# relay_board.net
KiCad netlist of a schematic drawn in EAGLE
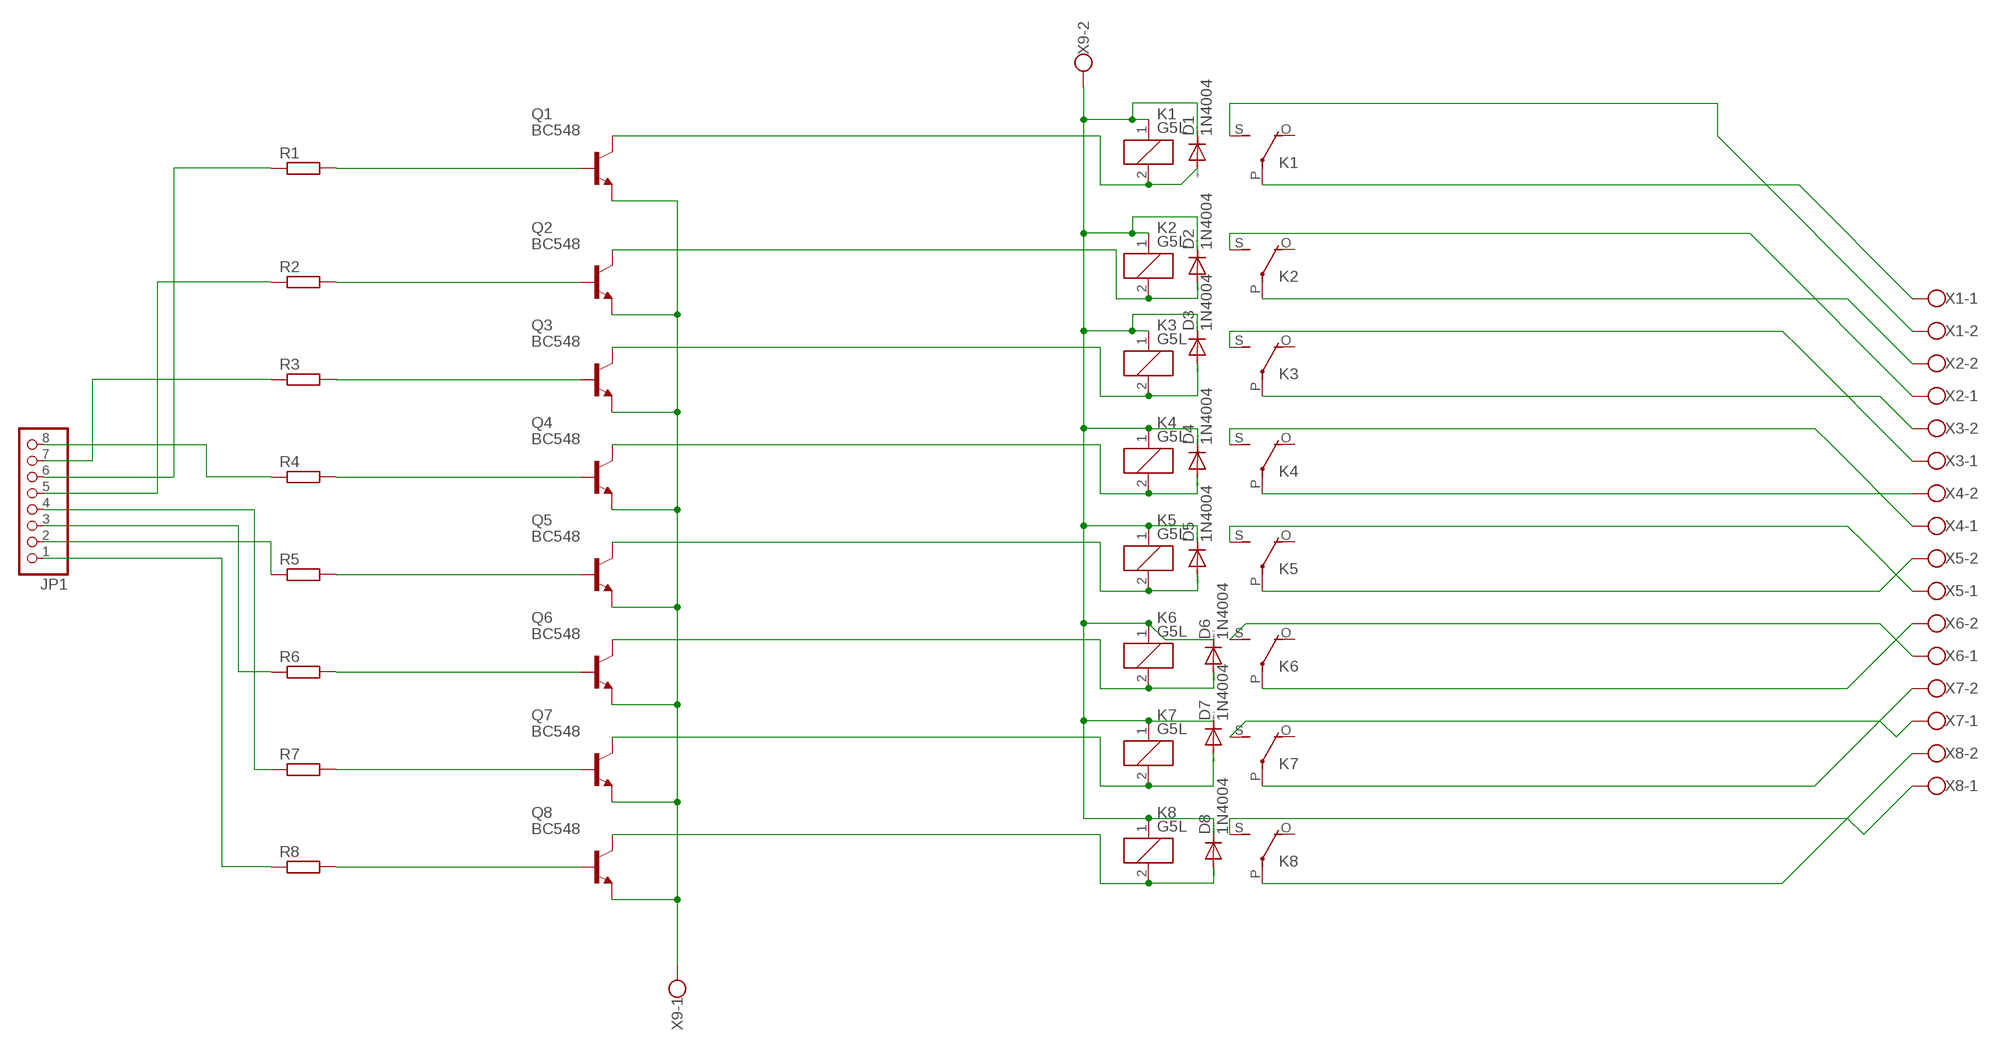
[diagram p0: schematic, sheet 1]

(export (version "E")
  (design (tool "Eeschema 10.0.6"))
  (components
    (comp (ref "D1")
      (value "1N4004")
      (footprint "eagle-import:DO41-10")
      (libsource (lib "eagle-import") (part "1N4004"))
    )
    (comp (ref "D2")
      (value "1N4004")
      (footprint "eagle-import:DO41-10")
      (libsource (lib "eagle-import") (part "1N4004"))
    )
    (comp (ref "D3")
      (value "1N4004")
      (footprint "eagle-import:DO41-10")
      (libsource (lib "eagle-import") (part "1N4004"))
    )
    (comp (ref "D4")
      (value "1N4004")
      (footprint "eagle-import:DO41-10")
      (libsource (lib "eagle-import") (part "1N4004"))
    )
    (comp (ref "D5")
      (value "1N4004")
      (footprint "eagle-import:DO41-10")
      (libsource (lib "eagle-import") (part "1N4004"))
    )
    (comp (ref "D6")
      (value "1N4004")
      (footprint "eagle-import:DO41-10")
      (libsource (lib "eagle-import") (part "1N4004"))
    )
    (comp (ref "D7")
      (value "1N4004")
      (footprint "eagle-import:DO41-10")
      (libsource (lib "eagle-import") (part "1N4004"))
    )
    (comp (ref "D8")
      (value "1N4004")
      (footprint "eagle-import:DO41-10")
      (libsource (lib "eagle-import") (part "1N4004"))
    )
    (comp (ref "JP1")
      (value "PINHD-1X8")
      (footprint "eagle-import:1X08")
      (libsource (lib "eagle-import") (part "PINHD-1X8"))
    )
    (comp (ref "K1")
      (value "G5L")
      (footprint "eagle-import:G5LE")
      (libsource (lib "eagle-import") (part "G5L"))
    )
    (comp (ref "K2")
      (value "G5L")
      (footprint "eagle-import:G5LE")
      (libsource (lib "eagle-import") (part "G5L"))
    )
    (comp (ref "K3")
      (value "G5L")
      (footprint "eagle-import:G5LE")
      (libsource (lib "eagle-import") (part "G5L"))
    )
    (comp (ref "K4")
      (value "G5L")
      (footprint "eagle-import:G5LE")
      (libsource (lib "eagle-import") (part "G5L"))
    )
    (comp (ref "K5")
      (value "G5L")
      (footprint "eagle-import:G5LE")
      (libsource (lib "eagle-import") (part "G5L"))
    )
    (comp (ref "K6")
      (value "G5L")
      (footprint "eagle-import:G5LE")
      (libsource (lib "eagle-import") (part "G5L"))
    )
    (comp (ref "K7")
      (value "G5L")
      (footprint "eagle-import:G5LE")
      (libsource (lib "eagle-import") (part "G5L"))
    )
    (comp (ref "K8")
      (value "G5L")
      (footprint "eagle-import:G5LE")
      (libsource (lib "eagle-import") (part "G5L"))
    )
    (comp (ref "Q1")
      (value "BC548")
      (footprint "eagle-import:TO92-EBC")
      (libsource (lib "eagle-import") (part "BC548"))
    )
    (comp (ref "Q2")
      (value "BC548")
      (footprint "eagle-import:TO92-EBC")
      (libsource (lib "eagle-import") (part "BC548"))
    )
    (comp (ref "Q3")
      (value "BC548")
      (footprint "eagle-import:TO92-EBC")
      (libsource (lib "eagle-import") (part "BC548"))
    )
    (comp (ref "Q4")
      (value "BC548")
      (footprint "eagle-import:TO92-EBC")
      (libsource (lib "eagle-import") (part "BC548"))
    )
    (comp (ref "Q5")
      (value "BC548")
      (footprint "eagle-import:TO92-EBC")
      (libsource (lib "eagle-import") (part "BC548"))
    )
    (comp (ref "Q6")
      (value "BC548")
      (footprint "eagle-import:TO92-EBC")
      (libsource (lib "eagle-import") (part "BC548"))
    )
    (comp (ref "Q7")
      (value "BC548")
      (footprint "eagle-import:TO92-EBC")
      (libsource (lib "eagle-import") (part "BC548"))
    )
    (comp (ref "Q8")
      (value "BC548")
      (footprint "eagle-import:TO92-EBC")
      (libsource (lib "eagle-import") (part "BC548"))
    )
    (comp (ref "R1")
      (value "RCL_R-EU_0207/10")
      (footprint "eagle-import:RCL_0207_10")
      (libsource (lib "eagle-import") (part "RCL_R-EU_0207/10"))
    )
    (comp (ref "R2")
      (value "RCL_R-EU_0207/10")
      (footprint "eagle-import:RCL_0207_10")
      (libsource (lib "eagle-import") (part "RCL_R-EU_0207/10"))
    )
    (comp (ref "R3")
      (value "RCL_R-EU_0207/10")
      (footprint "eagle-import:RCL_0207_10")
      (libsource (lib "eagle-import") (part "RCL_R-EU_0207/10"))
    )
    (comp (ref "R4")
      (value "RCL_R-EU_0207/10")
      (footprint "eagle-import:RCL_0207_10")
      (libsource (lib "eagle-import") (part "RCL_R-EU_0207/10"))
    )
    (comp (ref "R5")
      (value "RCL_R-EU_0207/10")
      (footprint "eagle-import:RCL_0207_10")
      (libsource (lib "eagle-import") (part "RCL_R-EU_0207/10"))
    )
    (comp (ref "R6")
      (value "RCL_R-EU_0207/10")
      (footprint "eagle-import:RCL_0207_10")
      (libsource (lib "eagle-import") (part "RCL_R-EU_0207/10"))
    )
    (comp (ref "R7")
      (value "RCL_R-EU_0207/10")
      (footprint "eagle-import:RCL_0207_10")
      (libsource (lib "eagle-import") (part "RCL_R-EU_0207/10"))
    )
    (comp (ref "R8")
      (value "RCL_R-EU_0207/10")
      (footprint "eagle-import:RCL_0207_10")
      (libsource (lib "eagle-import") (part "RCL_R-EU_0207/10"))
    )
    (comp (ref "X1")
      (value "W237-102")
      (footprint "eagle-import:W237-102")
      (fields (field (name "MPN") "237-102"))
      (libsource (lib "eagle-import") (part "W237-102"))
    )
    (comp (ref "X2")
      (value "W237-102")
      (footprint "eagle-import:W237-102")
      (fields (field (name "MPN") "237-102"))
      (libsource (lib "eagle-import") (part "W237-102"))
    )
    (comp (ref "X3")
      (value "W237-102")
      (footprint "eagle-import:W237-102")
      (fields (field (name "MPN") "237-102"))
      (libsource (lib "eagle-import") (part "W237-102"))
    )
    (comp (ref "X4")
      (value "W237-102")
      (footprint "eagle-import:W237-102")
      (fields (field (name "MPN") "237-102"))
      (libsource (lib "eagle-import") (part "W237-102"))
    )
    (comp (ref "X5")
      (value "W237-102")
      (footprint "eagle-import:W237-102")
      (fields (field (name "MPN") "237-102"))
      (libsource (lib "eagle-import") (part "W237-102"))
    )
    (comp (ref "X6")
      (value "W237-102")
      (footprint "eagle-import:W237-102")
      (fields (field (name "MPN") "237-102"))
      (libsource (lib "eagle-import") (part "W237-102"))
    )
    (comp (ref "X7")
      (value "W237-102")
      (footprint "eagle-import:W237-102")
      (fields (field (name "MPN") "237-102"))
      (libsource (lib "eagle-import") (part "W237-102"))
    )
    (comp (ref "X8")
      (value "W237-102")
      (footprint "eagle-import:W237-102")
      (fields (field (name "MPN") "237-102"))
      (libsource (lib "eagle-import") (part "W237-102"))
    )
    (comp (ref "X9")
      (value "W237-102")
      (footprint "eagle-import:W237-102")
      (fields (field (name "MPN") "237-102"))
      (libsource (lib "eagle-import") (part "W237-102"))
    )
  )
  (nets
    (net (code "1") (name "Net-(D1-PadA)") (class "Default")
      (node (ref "D1") (pin "A") (pinfunction "A_A") (pintype "passive"))
      (node (ref "K1") (pin "2") (pinfunction "2_2") (pintype "passive"))
      (node (ref "Q1") (pin "C") (pinfunction "C_C") (pintype "passive"))
    )
    (net (code "2") (name "Net-(D2-PadA)") (class "Default")
      (node (ref "D2") (pin "A") (pinfunction "A_A") (pintype "passive"))
      (node (ref "K2") (pin "2") (pinfunction "2_2") (pintype "passive"))
      (node (ref "Q2") (pin "C") (pinfunction "C_C") (pintype "passive"))
    )
    (net (code "3") (name "Net-(D3-PadA)") (class "Default")
      (node (ref "D3") (pin "A") (pinfunction "A_A") (pintype "passive"))
      (node (ref "K3") (pin "2") (pinfunction "2_2") (pintype "passive"))
      (node (ref "Q3") (pin "C") (pinfunction "C_C") (pintype "passive"))
    )
    (net (code "4") (name "Net-(D4-PadA)") (class "Default")
      (node (ref "D4") (pin "A") (pinfunction "A_A") (pintype "passive"))
      (node (ref "K4") (pin "2") (pinfunction "2_2") (pintype "passive"))
      (node (ref "Q4") (pin "C") (pinfunction "C_C") (pintype "passive"))
    )
    (net (code "5") (name "Net-(D5-PadA)") (class "Default")
      (node (ref "D5") (pin "A") (pinfunction "A_A") (pintype "passive"))
      (node (ref "K5") (pin "2") (pinfunction "2_2") (pintype "passive"))
      (node (ref "Q5") (pin "C") (pinfunction "C_C") (pintype "passive"))
    )
    (net (code "6") (name "Net-(D6-PadA)") (class "Default")
      (node (ref "D6") (pin "A") (pinfunction "A_A") (pintype "passive"))
      (node (ref "K6") (pin "2") (pinfunction "2_2") (pintype "passive"))
      (node (ref "Q6") (pin "C") (pinfunction "C_C") (pintype "passive"))
    )
    (net (code "7") (name "Net-(D7-PadA)") (class "Default")
      (node (ref "D7") (pin "A") (pinfunction "A_A") (pintype "passive"))
      (node (ref "K7") (pin "2") (pinfunction "2_2") (pintype "passive"))
      (node (ref "Q7") (pin "C") (pinfunction "C_C") (pintype "passive"))
    )
    (net (code "8") (name "Net-(D8-PadA)") (class "Default")
      (node (ref "D8") (pin "A") (pinfunction "A_A") (pintype "passive"))
      (node (ref "K8") (pin "2") (pinfunction "2_2") (pintype "passive"))
      (node (ref "Q8") (pin "C") (pinfunction "C_C") (pintype "passive"))
    )
    (net (code "9") (name "Net-(JP1-Pad1)") (class "Default")
      (node (ref "JP1") (pin "1") (pinfunction "1_1") (pintype "passive"))
      (node (ref "R8") (pin "1") (pinfunction "1_1") (pintype "passive"))
    )
    (net (code "10") (name "Net-(JP1-Pad2)") (class "Default")
      (node (ref "JP1") (pin "2") (pinfunction "2_2") (pintype "passive"))
      (node (ref "R5") (pin "1") (pinfunction "1_1") (pintype "passive"))
    )
    (net (code "11") (name "Net-(JP1-Pad3)") (class "Default")
      (node (ref "JP1") (pin "3") (pinfunction "3_3") (pintype "passive"))
      (node (ref "R6") (pin "1") (pinfunction "1_1") (pintype "passive"))
    )
    (net (code "12") (name "Net-(JP1-Pad4)") (class "Default")
      (node (ref "JP1") (pin "4") (pinfunction "4_4") (pintype "passive"))
      (node (ref "R7") (pin "1") (pinfunction "1_1") (pintype "passive"))
    )
    (net (code "13") (name "Net-(JP1-Pad5)") (class "Default")
      (node (ref "JP1") (pin "5") (pinfunction "5_5") (pintype "passive"))
      (node (ref "R2") (pin "1") (pinfunction "1_1") (pintype "passive"))
    )
    (net (code "14") (name "Net-(JP1-Pad6)") (class "Default")
      (node (ref "JP1") (pin "6") (pinfunction "6_6") (pintype "passive"))
      (node (ref "R1") (pin "1") (pinfunction "1_1") (pintype "passive"))
    )
    (net (code "15") (name "Net-(JP1-Pad7)") (class "Default")
      (node (ref "JP1") (pin "7") (pinfunction "7_7") (pintype "passive"))
      (node (ref "R3") (pin "1") (pinfunction "1_1") (pintype "passive"))
    )
    (net (code "16") (name "Net-(JP1-Pad8)") (class "Default")
      (node (ref "JP1") (pin "8") (pinfunction "8_8") (pintype "passive"))
      (node (ref "R4") (pin "1") (pinfunction "1_1") (pintype "passive"))
    )
    (net (code "17") (name "Net-(Q1-PadB)") (class "Default")
      (node (ref "Q1") (pin "B") (pinfunction "B_B") (pintype "passive"))
      (node (ref "R1") (pin "2") (pinfunction "2_2") (pintype "passive"))
    )
    (net (code "18") (name "Net-(Q2-PadB)") (class "Default")
      (node (ref "Q2") (pin "B") (pinfunction "B_B") (pintype "passive"))
      (node (ref "R2") (pin "2") (pinfunction "2_2") (pintype "passive"))
    )
    (net (code "19") (name "Net-(Q3-PadB)") (class "Default")
      (node (ref "Q3") (pin "B") (pinfunction "B_B") (pintype "passive"))
      (node (ref "R3") (pin "2") (pinfunction "2_2") (pintype "passive"))
    )
    (net (code "20") (name "Net-(Q4-PadB)") (class "Default")
      (node (ref "Q4") (pin "B") (pinfunction "B_B") (pintype "passive"))
      (node (ref "R4") (pin "2") (pinfunction "2_2") (pintype "passive"))
    )
    (net (code "21") (name "Net-(Q5-PadB)") (class "Default")
      (node (ref "Q5") (pin "B") (pinfunction "B_B") (pintype "passive"))
      (node (ref "R5") (pin "2") (pinfunction "2_2") (pintype "passive"))
    )
    (net (code "22") (name "Net-(Q6-PadB)") (class "Default")
      (node (ref "Q6") (pin "B") (pinfunction "B_B") (pintype "passive"))
      (node (ref "R6") (pin "2") (pinfunction "2_2") (pintype "passive"))
    )
    (net (code "23") (name "Net-(Q7-PadB)") (class "Default")
      (node (ref "Q7") (pin "B") (pinfunction "B_B") (pintype "passive"))
      (node (ref "R7") (pin "2") (pinfunction "2_2") (pintype "passive"))
    )
    (net (code "24") (name "Net-(Q8-PadB)") (class "Default")
      (node (ref "Q8") (pin "B") (pinfunction "B_B") (pintype "passive"))
      (node (ref "R8") (pin "2") (pinfunction "2_2") (pintype "passive"))
    )
    (net (code "25") (name "Net-(X1A-KL)") (class "Default")
      (node (ref "K1") (pin "P") (pinfunction "P_P") (pintype "passive"))
      (node (ref "X1") (pin "1") (pinfunction "KL_1") (pintype "passive"))
    )
    (net (code "26") (name "Net-(X1B-KL)") (class "Default")
      (node (ref "K1") (pin "S") (pinfunction "S_S") (pintype "passive"))
      (node (ref "X1") (pin "2") (pinfunction "KL_2") (pintype "passive"))
    )
    (net (code "27") (name "Net-(X2A-KL)") (class "Default")
      (node (ref "K2") (pin "S") (pinfunction "S_S") (pintype "passive"))
      (node (ref "X2") (pin "1") (pinfunction "KL_1") (pintype "passive"))
    )
    (net (code "28") (name "Net-(X2B-KL)") (class "Default")
      (node (ref "K2") (pin "P") (pinfunction "P_P") (pintype "passive"))
      (node (ref "X2") (pin "2") (pinfunction "KL_2") (pintype "passive"))
    )
    (net (code "29") (name "Net-(X3A-KL)") (class "Default")
      (node (ref "K3") (pin "S") (pinfunction "S_S") (pintype "passive"))
      (node (ref "X3") (pin "1") (pinfunction "KL_1") (pintype "passive"))
    )
    (net (code "30") (name "Net-(X3B-KL)") (class "Default")
      (node (ref "K3") (pin "P") (pinfunction "P_P") (pintype "passive"))
      (node (ref "X3") (pin "2") (pinfunction "KL_2") (pintype "passive"))
    )
    (net (code "31") (name "Net-(X4A-KL)") (class "Default")
      (node (ref "K4") (pin "S") (pinfunction "S_S") (pintype "passive"))
      (node (ref "X4") (pin "1") (pinfunction "KL_1") (pintype "passive"))
    )
    (net (code "32") (name "Net-(X4B-KL)") (class "Default")
      (node (ref "K4") (pin "P") (pinfunction "P_P") (pintype "passive"))
      (node (ref "X4") (pin "2") (pinfunction "KL_2") (pintype "passive"))
    )
    (net (code "33") (name "Net-(X5A-KL)") (class "Default")
      (node (ref "K5") (pin "S") (pinfunction "S_S") (pintype "passive"))
      (node (ref "X5") (pin "1") (pinfunction "KL_1") (pintype "passive"))
    )
    (net (code "34") (name "Net-(X5B-KL)") (class "Default")
      (node (ref "K5") (pin "P") (pinfunction "P_P") (pintype "passive"))
      (node (ref "X5") (pin "2") (pinfunction "KL_2") (pintype "passive"))
    )
    (net (code "35") (name "Net-(X6A-KL)") (class "Default")
      (node (ref "K6") (pin "S") (pinfunction "S_S") (pintype "passive"))
      (node (ref "X6") (pin "1") (pinfunction "KL_1") (pintype "passive"))
    )
    (net (code "36") (name "Net-(X6B-KL)") (class "Default")
      (node (ref "K6") (pin "P") (pinfunction "P_P") (pintype "passive"))
      (node (ref "X6") (pin "2") (pinfunction "KL_2") (pintype "passive"))
    )
    (net (code "37") (name "Net-(X7A-KL)") (class "Default")
      (node (ref "K7") (pin "S") (pinfunction "S_S") (pintype "passive"))
      (node (ref "X7") (pin "1") (pinfunction "KL_1") (pintype "passive"))
    )
    (net (code "38") (name "Net-(X7B-KL)") (class "Default")
      (node (ref "K7") (pin "P") (pinfunction "P_P") (pintype "passive"))
      (node (ref "X7") (pin "2") (pinfunction "KL_2") (pintype "passive"))
    )
    (net (code "39") (name "Net-(X8A-KL)") (class "Default")
      (node (ref "K8") (pin "S") (pinfunction "S_S") (pintype "passive"))
      (node (ref "X8") (pin "1") (pinfunction "KL_1") (pintype "passive"))
    )
    (net (code "40") (name "Net-(X8B-KL)") (class "Default")
      (node (ref "K8") (pin "P") (pinfunction "P_P") (pintype "passive"))
      (node (ref "X8") (pin "2") (pinfunction "KL_2") (pintype "passive"))
    )
    (net (code "41") (name "Net-(X9A-KL)") (class "Default")
      (node (ref "Q1") (pin "E") (pinfunction "E_E") (pintype "passive"))
      (node (ref "Q2") (pin "E") (pinfunction "E_E") (pintype "passive"))
      (node (ref "Q3") (pin "E") (pinfunction "E_E") (pintype "passive"))
      (node (ref "Q4") (pin "E") (pinfunction "E_E") (pintype "passive"))
      (node (ref "Q5") (pin "E") (pinfunction "E_E") (pintype "passive"))
      (node (ref "Q6") (pin "E") (pinfunction "E_E") (pintype "passive"))
      (node (ref "Q7") (pin "E") (pinfunction "E_E") (pintype "passive"))
      (node (ref "Q8") (pin "E") (pinfunction "E_E") (pintype "passive"))
      (node (ref "X9") (pin "1") (pinfunction "KL_1") (pintype "passive"))
    )
    (net (code "42") (name "Net-(X9B-KL)") (class "Default")
      (node (ref "D1") (pin "C") (pinfunction "C_C") (pintype "passive"))
      (node (ref "D2") (pin "C") (pinfunction "C_C") (pintype "passive"))
      (node (ref "D3") (pin "C") (pinfunction "C_C") (pintype "passive"))
      (node (ref "D4") (pin "C") (pinfunction "C_C") (pintype "passive"))
      (node (ref "D5") (pin "C") (pinfunction "C_C") (pintype "passive"))
      (node (ref "D6") (pin "C") (pinfunction "C_C") (pintype "passive"))
      (node (ref "D7") (pin "C") (pinfunction "C_C") (pintype "passive"))
      (node (ref "D8") (pin "C") (pinfunction "C_C") (pintype "passive"))
      (node (ref "K1") (pin "1") (pinfunction "1_1") (pintype "passive"))
      (node (ref "K2") (pin "1") (pinfunction "1_1") (pintype "passive"))
      (node (ref "K3") (pin "1") (pinfunction "1_1") (pintype "passive"))
      (node (ref "K4") (pin "1") (pinfunction "1_1") (pintype "passive"))
      (node (ref "K5") (pin "1") (pinfunction "1_1") (pintype "passive"))
      (node (ref "K6") (pin "1") (pinfunction "1_1") (pintype "passive"))
      (node (ref "K7") (pin "1") (pinfunction "1_1") (pintype "passive"))
      (node (ref "K8") (pin "1") (pinfunction "1_1") (pintype "passive"))
      (node (ref "X9") (pin "2") (pinfunction "KL_2") (pintype "passive"))
    )
    (net (code "43") (name "unconnected-(K1-PadO)") (class "Default")
      (node (ref "K1") (pin "O") (pinfunction "O_O") (pintype "passive"))
    )
    (net (code "44") (name "unconnected-(K2-PadO)") (class "Default")
      (node (ref "K2") (pin "O") (pinfunction "O_O") (pintype "passive"))
    )
    (net (code "45") (name "unconnected-(K3-PadO)") (class "Default")
      (node (ref "K3") (pin "O") (pinfunction "O_O") (pintype "passive"))
    )
    (net (code "46") (name "unconnected-(K4-PadO)") (class "Default")
      (node (ref "K4") (pin "O") (pinfunction "O_O") (pintype "passive"))
    )
    (net (code "47") (name "unconnected-(K5-PadO)") (class "Default")
      (node (ref "K5") (pin "O") (pinfunction "O_O") (pintype "passive"))
    )
    (net (code "48") (name "unconnected-(K6-PadO)") (class "Default")
      (node (ref "K6") (pin "O") (pinfunction "O_O") (pintype "passive"))
    )
    (net (code "49") (name "unconnected-(K7-PadO)") (class "Default")
      (node (ref "K7") (pin "O") (pinfunction "O_O") (pintype "passive"))
    )
    (net (code "50") (name "unconnected-(K8-PadO)") (class "Default")
      (node (ref "K8") (pin "O") (pinfunction "O_O") (pintype "passive"))
    )
  )
)
